# SerialDev-2232-1A.net
KiCad netlist of a schematic drawn in EAGLE
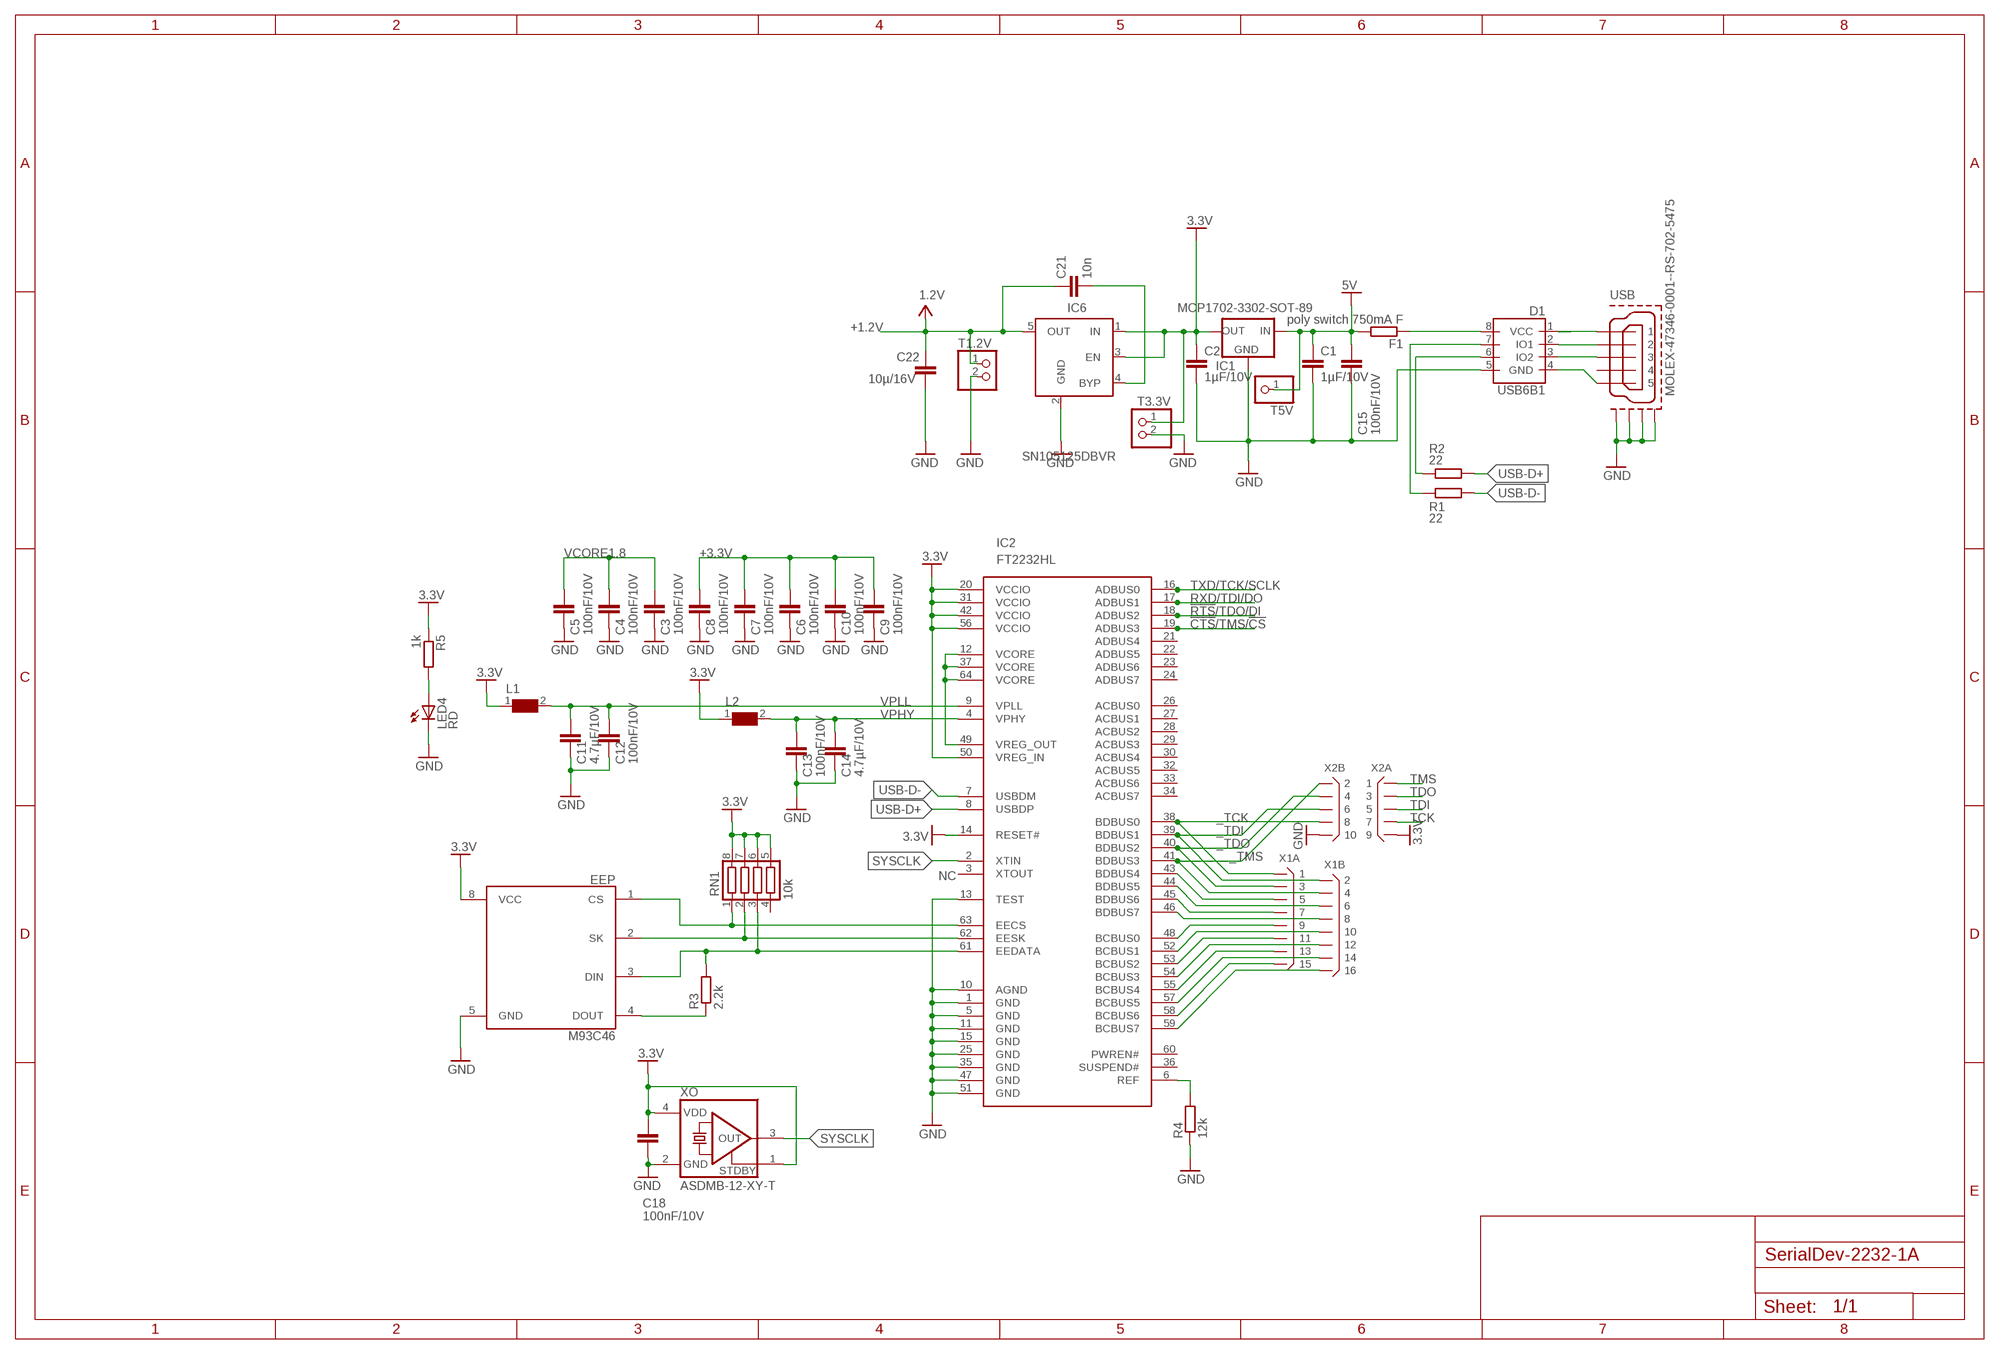
[diagram p0: schematic, sheet 1]

(export (version "E")
  (design (tool "Eeschema 10.0.6"))
  (components
    (comp (ref "C1")
      (value "1µF/10V")
      (footprint "eagle-import:C0805K")
      (libsource (lib "eagle-import") (part "C-EUC0805K"))
    )
    (comp (ref "C2")
      (value "1µF/10V")
      (footprint "eagle-import:C0805K")
      (libsource (lib "eagle-import") (part "C-EUC0805K"))
    )
    (comp (ref "C3")
      (value "100nF/10V")
      (footprint "eagle-import:C0402K")
      (libsource (lib "eagle-import") (part "C-EUC0402K"))
    )
    (comp (ref "C4")
      (value "100nF/10V")
      (footprint "eagle-import:C0402K")
      (libsource (lib "eagle-import") (part "C-EUC0402K"))
    )
    (comp (ref "C5")
      (value "100nF/10V")
      (footprint "eagle-import:C0402K")
      (libsource (lib "eagle-import") (part "C-EUC0402K"))
    )
    (comp (ref "C6")
      (value "100nF/10V")
      (footprint "eagle-import:C0402K")
      (libsource (lib "eagle-import") (part "C-EUC0402K"))
    )
    (comp (ref "C7")
      (value "100nF/10V")
      (footprint "eagle-import:C0402K")
      (libsource (lib "eagle-import") (part "C-EUC0402K"))
    )
    (comp (ref "C8")
      (value "100nF/10V")
      (footprint "eagle-import:C0402K")
      (libsource (lib "eagle-import") (part "C-EUC0402K"))
    )
    (comp (ref "C9")
      (value "100nF/10V")
      (footprint "eagle-import:C0402K")
      (libsource (lib "eagle-import") (part "C-EUC0402K"))
    )
    (comp (ref "C10")
      (value "100nF/10V")
      (footprint "eagle-import:C0402K")
      (libsource (lib "eagle-import") (part "C-EUC0402K"))
    )
    (comp (ref "C11")
      (value "4.7µF/10V")
      (footprint "eagle-import:C0402K")
      (libsource (lib "eagle-import") (part "C-EUC0402K"))
    )
    (comp (ref "C12")
      (value "100nF/10V")
      (footprint "eagle-import:C0402K")
      (libsource (lib "eagle-import") (part "C-EUC0402K"))
    )
    (comp (ref "C13")
      (value "100nF/10V")
      (footprint "eagle-import:C0402K")
      (libsource (lib "eagle-import") (part "C-EUC0402K"))
    )
    (comp (ref "C14")
      (value "4.7µF/10V")
      (footprint "eagle-import:C0402K")
      (libsource (lib "eagle-import") (part "C-EUC0402K"))
    )
    (comp (ref "C15")
      (value "100nF/10V")
      (footprint "eagle-import:C0402K")
      (libsource (lib "eagle-import") (part "C-EUC0402K"))
    )
    (comp (ref "C18")
      (value "100nF/10V")
      (footprint "eagle-import:C0402K")
      (libsource (lib "eagle-import") (part "C-EUC0402K"))
    )
    (comp (ref "C21")
      (value "10n")
      (footprint "eagle-import:C0805K")
      (fields (field (name "PARTNO") "Kemet: C1206C103K5RACTU"))
      (libsource (lib "eagle-import") (part "C-EUC0805K"))
    )
    (comp (ref "C22")
      (value "10µ/16V")
      (footprint "eagle-import:C0805K")
      (fields (field (name "PARTNO") "Vishay Sprague: TR3B106K016C0800"))
      (libsource (lib "eagle-import") (part "C-EUC0805K"))
    )
    (comp (ref "D1")
      (value "USB6B1")
      (footprint "eagle-import:SO08")
      (libsource (lib "eagle-import") (part "USB6B1"))
    )
    (comp (ref "EEP")
      (value "M93C46")
      (footprint "eagle-import:SO08")
      (libsource (lib "eagle-import") (part "M93C46"))
    )
    (comp (ref "F1")
      (value "poly switch 750mA F")
      (footprint "eagle-import:R1206")
      (libsource (lib "eagle-import") (part "R-EU_R1206"))
    )
    (comp (ref "IC1")
      (value "MCP1702-3302-SOT-89")
      (footprint "eagle-import:SOT89-R")
      (libsource (lib "eagle-import") (part "MCP1702--SOT-893302"))
    )
    (comp (ref "IC2")
      (value "FT2232HL")
      (footprint "eagle-import:LQFP-ST-64-2")
      (libsource (lib "eagle-import") (part "FT2232HL"))
    )
    (comp (ref "IC6")
      (value "SN105125DBVR")
      (footprint "eagle-import:SOT23-5")
      (fields (field (name "PARTNO") "LINEAR TECHNOLOGY: LT1761ES5-1.2"))
      (libsource (lib "eagle-import") (part "MIC5219XX"))
    )
    (comp (ref "L1")
      (value "WE-CBF_0603")
      (footprint "eagle-import:0603")
      (libsource (lib "eagle-import") (part "WE-CBF_0603"))
    )
    (comp (ref "L2")
      (value "WE-CBF_0603")
      (footprint "eagle-import:0603")
      (libsource (lib "eagle-import") (part "WE-CBF_0603"))
    )
    (comp (ref "LED4")
      (value "RD")
      (footprint "eagle-import:CHIP-LED0805")
      (libsource (lib "eagle-import") (part "LEDCHIP-LED0805"))
    )
    (comp (ref "R1")
      (value "22")
      (footprint "eagle-import:R0603")
      (libsource (lib "eagle-import") (part "R-EU_R0603"))
    )
    (comp (ref "R2")
      (value "22")
      (footprint "eagle-import:R0603")
      (libsource (lib "eagle-import") (part "R-EU_R0603"))
    )
    (comp (ref "R3")
      (value "2.2k")
      (footprint "eagle-import:R0603")
      (libsource (lib "eagle-import") (part "R-EU_R0603"))
    )
    (comp (ref "R4")
      (value "12k")
      (footprint "eagle-import:R0603")
      (libsource (lib "eagle-import") (part "R-EU_R0603"))
    )
    (comp (ref "R5")
      (value "1k")
      (footprint "eagle-import:R0603")
      (libsource (lib "eagle-import") (part "R-EU_R0603"))
    )
    (comp (ref "RN1")
      (value "10k")
      (footprint "eagle-import:CTS742C083")
      (libsource (lib "eagle-import") (part "CTS742C083"))
    )
    (comp (ref "T1.2V")
      (value "PINHD-1X2")
      (footprint "eagle-import:1X02")
      (libsource (lib "eagle-import") (part "PINHD-1X2"))
    )
    (comp (ref "T3.3V")
      (value "PINHD-1X2")
      (footprint "eagle-import:1X02")
      (libsource (lib "eagle-import") (part "PINHD-1X2"))
    )
    (comp (ref "T5V")
      (value "PINHD-1X1")
      (footprint "eagle-import:1X01")
      (libsource (lib "eagle-import") (part "PINHD-1X1"))
    )
    (comp (ref "USB")
      (value "MOLEX-47346-0001--RS-702-5475")
      (footprint "eagle-import:MOLEX-47364-0001")
      (libsource (lib "eagle-import") (part "MOLEX-47346-0001"))
    )
    (comp (ref "X1")
      (value "X08X2IR")
      (footprint "eagle-import:X16R-IDC")
      (libsource (lib "eagle-import") (part "X08X2IR"))
    )
    (comp (ref "X2")
      (value "X05X2DR")
      (footprint "eagle-import:X10R-DIL")
      (libsource (lib "eagle-import") (part "X05X2DR"))
    )
    (comp (ref "XO")
      (value "ASDMB-12-XY-T")
      (footprint "eagle-import:XO-4-2.5X2.0")
      (fields (field (name "MFG") "ABRACON") (field (name "MFG_PARTNO") "ASDMB-12.000MHZ-XY-T"))
      (libsource (lib "eagle-import") (part "XTAL-ASDMB"))
    )
  )
  (nets
    (net (code "1") (name "/RXD{slash}TDI{slash}DO") (class "Default")
      (node (ref "IC2") (pin "17") (pinfunction "ADBUS1_17") (pintype "bidirectional"))
    )
    (net (code "2") (name "/TCK") (class "Default")
      (node (ref "X2") (pin "7") (pinfunction "7_7") (pintype "bidirectional"))
    )
    (net (code "3") (name "/TDI") (class "Default")
      (node (ref "X2") (pin "5") (pinfunction "5_5") (pintype "bidirectional"))
    )
    (net (code "4") (name "/TDO") (class "Default")
      (node (ref "X2") (pin "3") (pinfunction "3_3") (pintype "bidirectional"))
    )
    (net (code "5") (name "/TMS") (class "Default")
      (node (ref "X2") (pin "1") (pinfunction "1_1") (pintype "bidirectional"))
    )
    (net (code "6") (name "/TXD{slash}TCK{slash}SCLK") (class "Default")
      (node (ref "IC2") (pin "16") (pinfunction "ADBUS0_16") (pintype "bidirectional"))
    )
    (net (code "7") (name "/VCORE1.8") (class "Default")
      (node (ref "C3") (pin "1") (pinfunction "1_1") (pintype "passive"))
      (node (ref "C4") (pin "1") (pinfunction "1_1") (pintype "passive"))
      (node (ref "C5") (pin "1") (pinfunction "1_1") (pintype "passive"))
      (node (ref "IC2") (pin "12") (pinfunction "VCORE_12") (pintype "power_in"))
      (node (ref "IC2") (pin "37") (pinfunction "VCORE_37") (pintype "power_in"))
      (node (ref "IC2") (pin "49") (pinfunction "VREG_OUT_49") (pintype "output"))
      (node (ref "IC2") (pin "64") (pinfunction "VCORE_64") (pintype "power_in"))
    )
    (net (code "8") (name "/VPHY") (class "Default")
      (node (ref "C13") (pin "1") (pinfunction "1_1") (pintype "passive"))
      (node (ref "C14") (pin "1") (pinfunction "1_1") (pintype "passive"))
      (node (ref "IC2") (pin "4") (pinfunction "VPHY_4") (pintype "power_in"))
      (node (ref "L2") (pin "2") (pinfunction "2_2") (pintype "passive"))
    )
    (net (code "9") (name "/VPLL") (class "Default")
      (node (ref "C11") (pin "1") (pinfunction "1_1") (pintype "passive"))
      (node (ref "C12") (pin "1") (pinfunction "1_1") (pintype "passive"))
      (node (ref "IC2") (pin "9") (pinfunction "VPLL_9") (pintype "power_in"))
      (node (ref "L1") (pin "2") (pinfunction "2_2") (pintype "passive"))
    )
    (net (code "10") (name "/_TCK") (class "Default")
      (node (ref "IC2") (pin "38") (pinfunction "BDBUS0_38") (pintype "output"))
      (node (ref "X1") (pin "1") (pinfunction "1_1") (pintype "bidirectional"))
      (node (ref "X2") (pin "8") (pinfunction "8_8") (pintype "bidirectional"))
    )
    (net (code "11") (name "/_TDI") (class "Default")
      (node (ref "IC2") (pin "39") (pinfunction "BDBUS1_39") (pintype "input"))
      (node (ref "X1") (pin "2") (pinfunction "2_2") (pintype "bidirectional"))
      (node (ref "X2") (pin "6") (pinfunction "6_6") (pintype "bidirectional"))
    )
    (net (code "12") (name "/_TDO") (class "Default")
      (node (ref "IC2") (pin "40") (pinfunction "BDBUS2_40") (pintype "output"))
      (node (ref "X1") (pin "3") (pinfunction "3_3") (pintype "bidirectional"))
      (node (ref "X2") (pin "4") (pinfunction "4_4") (pintype "bidirectional"))
    )
    (net (code "13") (name "/_TMS") (class "Default")
      (node (ref "IC2") (pin "41") (pinfunction "BDBUS3_41") (pintype "input"))
      (node (ref "X1") (pin "4") (pinfunction "4_4") (pintype "bidirectional"))
      (node (ref "X2") (pin "2") (pinfunction "2_2") (pintype "bidirectional"))
    )
    (net (code "14") (name "/~{CTS}{slash}TMS{slash}~{CS}") (class "Default")
      (node (ref "IC2") (pin "19") (pinfunction "ADBUS3_19") (pintype "bidirectional"))
    )
    (net (code "15") (name "/~{RTS}{slash}TDO{slash}DI") (class "Default")
      (node (ref "IC2") (pin "18") (pinfunction "ADBUS2_18") (pintype "bidirectional"))
    )
    (net (code "16") (name "1.2V") (class "Default")
      (node (ref "C21") (pin "1") (pinfunction "1_1") (pintype "passive"))
      (node (ref "C22") (pin "1") (pinfunction "1_1") (pintype "passive"))
      (node (ref "IC6") (pin "5") (pinfunction "OUT_5") (pintype "output"))
      (node (ref "T1.2V") (pin "1") (pinfunction "1_1") (pintype "passive"))
    )
    (net (code "17") (name "3.3V") (class "Default")
      (node (ref "C10") (pin "1") (pinfunction "1_1") (pintype "passive"))
      (node (ref "C18") (pin "1") (pinfunction "1_1") (pintype "passive"))
      (node (ref "C2") (pin "1") (pinfunction "1_1") (pintype "passive"))
      (node (ref "C6") (pin "1") (pinfunction "1_1") (pintype "passive"))
      (node (ref "C7") (pin "1") (pinfunction "1_1") (pintype "passive"))
      (node (ref "C8") (pin "1") (pinfunction "1_1") (pintype "passive"))
      (node (ref "C9") (pin "1") (pinfunction "1_1") (pintype "passive"))
      (node (ref "EEP") (pin "8") (pinfunction "VCC_8") (pintype "bidirectional"))
      (node (ref "IC1") (pin "3") (pinfunction "OUT_3") (pintype "passive"))
      (node (ref "IC2") (pin "14") (pinfunction "RESET#_14") (pintype "bidirectional"))
      (node (ref "IC2") (pin "20") (pinfunction "VCCIO_20") (pintype "bidirectional"))
      (node (ref "IC2") (pin "31") (pinfunction "VCCIO_31") (pintype "power_in"))
      (node (ref "IC2") (pin "42") (pinfunction "VCCIO_42") (pintype "bidirectional"))
      (node (ref "IC2") (pin "50") (pinfunction "VREG_IN_50") (pintype "bidirectional"))
      (node (ref "IC2") (pin "56") (pinfunction "VCCIO_56") (pintype "bidirectional"))
      (node (ref "IC6") (pin "1") (pinfunction "IN_1") (pintype "input"))
      (node (ref "IC6") (pin "3") (pinfunction "EN_3") (pintype "input"))
      (node (ref "L1") (pin "1") (pinfunction "1_1") (pintype "passive"))
      (node (ref "L2") (pin "1") (pinfunction "1_1") (pintype "passive"))
      (node (ref "R5") (pin "1") (pinfunction "1_1") (pintype "passive"))
      (node (ref "RN1") (pin "5") (pinfunction "5_5") (pintype "passive"))
      (node (ref "RN1") (pin "6") (pinfunction "6_6") (pintype "passive"))
      (node (ref "RN1") (pin "7") (pinfunction "7_7") (pintype "passive"))
      (node (ref "RN1") (pin "8") (pinfunction "8_8") (pintype "passive"))
      (node (ref "T3.3V") (pin "1") (pinfunction "1_1") (pintype "passive"))
      (node (ref "X2") (pin "9") (pinfunction "9_9") (pintype "bidirectional"))
      (node (ref "XO") (pin "1") (pinfunction "TRI_1") (pintype "input"))
      (node (ref "XO") (pin "4") (pinfunction "VDD_4") (pintype "power_in"))
    )
    (net (code "18") (name "5V") (class "Default")
      (node (ref "C1") (pin "1") (pinfunction "1_1") (pintype "passive"))
      (node (ref "C15") (pin "1") (pinfunction "1_1") (pintype "passive"))
      (node (ref "F1") (pin "2") (pinfunction "2_2") (pintype "passive"))
      (node (ref "IC1") (pin "2") (pinfunction "IN_2") (pintype "input"))
      (node (ref "IC1") (pin "4") (pinfunction "IN_4") (pintype "input"))
      (node (ref "T5V") (pin "1") (pinfunction "1_1") (pintype "passive"))
    )
    (net (code "19") (name "GND") (class "Default")
      (node (ref "C1") (pin "2") (pinfunction "2_2") (pintype "passive"))
      (node (ref "C10") (pin "2") (pinfunction "2_2") (pintype "passive"))
      (node (ref "C11") (pin "2") (pinfunction "2_2") (pintype "passive"))
      (node (ref "C12") (pin "2") (pinfunction "2_2") (pintype "passive"))
      (node (ref "C13") (pin "2") (pinfunction "2_2") (pintype "passive"))
      (node (ref "C14") (pin "2") (pinfunction "2_2") (pintype "passive"))
      (node (ref "C15") (pin "2") (pinfunction "2_2") (pintype "passive"))
      (node (ref "C18") (pin "2") (pinfunction "2_2") (pintype "passive"))
      (node (ref "C2") (pin "2") (pinfunction "2_2") (pintype "passive"))
      (node (ref "C22") (pin "2") (pinfunction "2_2") (pintype "passive"))
      (node (ref "C3") (pin "2") (pinfunction "2_2") (pintype "passive"))
      (node (ref "C4") (pin "2") (pinfunction "2_2") (pintype "passive"))
      (node (ref "C5") (pin "2") (pinfunction "2_2") (pintype "passive"))
      (node (ref "C6") (pin "2") (pinfunction "2_2") (pintype "passive"))
      (node (ref "C7") (pin "2") (pinfunction "2_2") (pintype "passive"))
      (node (ref "C8") (pin "2") (pinfunction "2_2") (pintype "passive"))
      (node (ref "C9") (pin "2") (pinfunction "2_2") (pintype "passive"))
      (node (ref "D1") (pin "5") (pinfunction "GND_5") (pintype "power_in"))
      (node (ref "EEP") (pin "5") (pinfunction "GND_5") (pintype "bidirectional"))
      (node (ref "IC1") (pin "1") (pinfunction "GND_1") (pintype "input"))
      (node (ref "IC2") (pin "1") (pinfunction "GND_1") (pintype "power_in"))
      (node (ref "IC2") (pin "10") (pinfunction "AGND_10") (pintype "power_in"))
      (node (ref "IC2") (pin "11") (pinfunction "GND_11") (pintype "power_in"))
      (node (ref "IC2") (pin "13") (pinfunction "TEST_13") (pintype "input"))
      (node (ref "IC2") (pin "15") (pinfunction "GND_15") (pintype "bidirectional"))
      (node (ref "IC2") (pin "25") (pinfunction "GND_25") (pintype "bidirectional"))
      (node (ref "IC2") (pin "35") (pinfunction "GND_35") (pintype "bidirectional"))
      (node (ref "IC2") (pin "47") (pinfunction "GND_47") (pintype "bidirectional"))
      (node (ref "IC2") (pin "5") (pinfunction "GND_5") (pintype "power_in"))
      (node (ref "IC2") (pin "51") (pinfunction "GND_51") (pintype "bidirectional"))
      (node (ref "IC6") (pin "2") (pinfunction "GND_2") (pintype "power_in"))
      (node (ref "LED4") (pin "C") (pinfunction "C_C") (pintype "passive"))
      (node (ref "R4") (pin "1") (pinfunction "1_1") (pintype "passive"))
      (node (ref "T1.2V") (pin "2") (pinfunction "2_2") (pintype "passive"))
      (node (ref "T3.3V") (pin "2") (pinfunction "2_2") (pintype "passive"))
      (node (ref "USB") (pin "GND1") (pinfunction "GND1_GND1") (pintype "bidirectional"))
      (node (ref "USB") (pin "GND2") (pinfunction "GND2_GND2") (pintype "bidirectional"))
      (node (ref "USB") (pin "GND3") (pinfunction "GND3_GND3") (pintype "bidirectional"))
      (node (ref "USB") (pin "GND4") (pinfunction "GND4_GND4") (pintype "bidirectional"))
      (node (ref "X2") (pin "10") (pinfunction "10_10") (pintype "bidirectional"))
      (node (ref "XO") (pin "2") (pinfunction "GND_2") (pintype "power_in"))
    )
    (net (code "20") (name "Net-(D1-GND-Pad4)") (class "Default")
      (node (ref "D1") (pin "4") (pinfunction "GND_4") (pintype "power_in"))
      (node (ref "USB") (pin "5") (pinfunction "5_5") (pintype "input"))
    )
    (net (code "21") (name "Net-(D1-IO1-Pad2)") (class "Default")
      (node (ref "D1") (pin "2") (pinfunction "IO1_2") (pintype "bidirectional"))
      (node (ref "USB") (pin "2") (pinfunction "2_2") (pintype "input"))
    )
    (net (code "22") (name "Net-(D1-IO1-Pad7)") (class "Default")
      (node (ref "D1") (pin "7") (pinfunction "IO1_7") (pintype "bidirectional"))
      (node (ref "R1") (pin "2") (pinfunction "2_2") (pintype "passive"))
    )
    (net (code "23") (name "Net-(D1-IO2-Pad3)") (class "Default")
      (node (ref "D1") (pin "3") (pinfunction "IO2_3") (pintype "bidirectional"))
      (node (ref "USB") (pin "3") (pinfunction "3_3") (pintype "input"))
    )
    (net (code "24") (name "Net-(D1-IO2-Pad6)") (class "Default")
      (node (ref "D1") (pin "6") (pinfunction "IO2_6") (pintype "bidirectional"))
      (node (ref "R2") (pin "1") (pinfunction "1_1") (pintype "passive"))
    )
    (net (code "25") (name "Net-(D1-VCC-Pad1)") (class "Default")
      (node (ref "D1") (pin "1") (pinfunction "VCC_1") (pintype "power_in"))
      (node (ref "USB") (pin "1") (pinfunction "1_1") (pintype "input"))
    )
    (net (code "26") (name "Net-(D1-VCC-Pad8)") (class "Default")
      (node (ref "D1") (pin "8") (pinfunction "VCC_8") (pintype "power_in"))
      (node (ref "F1") (pin "1") (pinfunction "1_1") (pintype "passive"))
    )
    (net (code "27") (name "Net-(EEP-CS)") (class "Default")
      (node (ref "EEP") (pin "1") (pinfunction "CS_1") (pintype "bidirectional"))
      (node (ref "IC2") (pin "63") (pinfunction "EECS_63") (pintype "bidirectional"))
      (node (ref "RN1") (pin "1") (pinfunction "1_1") (pintype "passive"))
    )
    (net (code "28") (name "Net-(EEP-DIN)") (class "Default")
      (node (ref "EEP") (pin "3") (pinfunction "DIN_3") (pintype "bidirectional"))
      (node (ref "IC2") (pin "61") (pinfunction "EEDATA_61") (pintype "bidirectional"))
      (node (ref "R3") (pin "2") (pinfunction "2_2") (pintype "passive"))
      (node (ref "RN1") (pin "3") (pinfunction "3_3") (pintype "passive"))
    )
    (net (code "29") (name "Net-(EEP-DOUT)") (class "Default")
      (node (ref "EEP") (pin "4") (pinfunction "DOUT_4") (pintype "bidirectional"))
      (node (ref "R3") (pin "1") (pinfunction "1_1") (pintype "passive"))
    )
    (net (code "30") (name "Net-(EEP-SK)") (class "Default")
      (node (ref "EEP") (pin "2") (pinfunction "SK_2") (pintype "bidirectional"))
      (node (ref "IC2") (pin "62") (pinfunction "EESK_62") (pintype "bidirectional"))
      (node (ref "RN1") (pin "2") (pinfunction "2_2") (pintype "passive"))
    )
    (net (code "31") (name "Net-(IC2-BCBUS0)") (class "Default")
      (node (ref "IC2") (pin "48") (pinfunction "BCBUS0_48") (pintype "bidirectional"))
      (node (ref "X1") (pin "9") (pinfunction "9_9") (pintype "bidirectional"))
    )
    (net (code "32") (name "Net-(IC2-BCBUS1)") (class "Default")
      (node (ref "IC2") (pin "52") (pinfunction "BCBUS1_52") (pintype "bidirectional"))
      (node (ref "X1") (pin "10") (pinfunction "10_10") (pintype "bidirectional"))
    )
    (net (code "33") (name "Net-(IC2-BCBUS2)") (class "Default")
      (node (ref "IC2") (pin "53") (pinfunction "BCBUS2_53") (pintype "bidirectional"))
      (node (ref "X1") (pin "11") (pinfunction "11_11") (pintype "bidirectional"))
    )
    (net (code "34") (name "Net-(IC2-BCBUS3)") (class "Default")
      (node (ref "IC2") (pin "54") (pinfunction "BCBUS3_54") (pintype "bidirectional"))
      (node (ref "X1") (pin "12") (pinfunction "12_12") (pintype "bidirectional"))
    )
    (net (code "35") (name "Net-(IC2-BCBUS4)") (class "Default")
      (node (ref "IC2") (pin "55") (pinfunction "BCBUS4_55") (pintype "bidirectional"))
      (node (ref "X1") (pin "13") (pinfunction "13_13") (pintype "bidirectional"))
    )
    (net (code "36") (name "Net-(IC2-BCBUS5)") (class "Default")
      (node (ref "IC2") (pin "57") (pinfunction "BCBUS5_57") (pintype "bidirectional"))
      (node (ref "X1") (pin "14") (pinfunction "14_14") (pintype "bidirectional"))
    )
    (net (code "37") (name "Net-(IC2-BCBUS6)") (class "Default")
      (node (ref "IC2") (pin "58") (pinfunction "BCBUS6_58") (pintype "bidirectional"))
      (node (ref "X1") (pin "15") (pinfunction "15_15") (pintype "bidirectional"))
    )
    (net (code "38") (name "Net-(IC2-BCBUS7)") (class "Default")
      (node (ref "IC2") (pin "59") (pinfunction "BCBUS7_59") (pintype "bidirectional"))
      (node (ref "X1") (pin "16") (pinfunction "16_16") (pintype "bidirectional"))
    )
    (net (code "39") (name "Net-(IC2-BDBUS4)") (class "Default")
      (node (ref "IC2") (pin "43") (pinfunction "BDBUS4_43") (pintype "output"))
      (node (ref "X1") (pin "5") (pinfunction "5_5") (pintype "bidirectional"))
    )
    (net (code "40") (name "Net-(IC2-BDBUS5)") (class "Default")
      (node (ref "IC2") (pin "44") (pinfunction "BDBUS5_44") (pintype "input"))
      (node (ref "X1") (pin "6") (pinfunction "6_6") (pintype "bidirectional"))
    )
    (net (code "41") (name "Net-(IC2-BDBUS6)") (class "Default")
      (node (ref "IC2") (pin "45") (pinfunction "BDBUS6_45") (pintype "input"))
      (node (ref "X1") (pin "7") (pinfunction "7_7") (pintype "bidirectional"))
    )
    (net (code "42") (name "Net-(IC2-BDBUS7)") (class "Default")
      (node (ref "IC2") (pin "46") (pinfunction "BDBUS7_46") (pintype "input"))
      (node (ref "X1") (pin "8") (pinfunction "8_8") (pintype "bidirectional"))
    )
    (net (code "43") (name "Net-(IC2-REF)") (class "Default")
      (node (ref "IC2") (pin "6") (pinfunction "REF_6") (pintype "bidirectional"))
      (node (ref "R4") (pin "2") (pinfunction "2_2") (pintype "passive"))
    )
    (net (code "44") (name "Net-(IC6-BYP)") (class "Default")
      (node (ref "C21") (pin "2") (pinfunction "2_2") (pintype "passive"))
      (node (ref "IC6") (pin "4") (pinfunction "BYP_4") (pintype "passive"))
    )
    (net (code "45") (name "Net-(LED4-PadA)") (class "Default")
      (node (ref "LED4") (pin "A") (pinfunction "A_A") (pintype "passive"))
      (node (ref "R5") (pin "2") (pinfunction "2_2") (pintype "passive"))
    )
    (net (code "46") (name "SYSCLK") (class "Default")
      (node (ref "IC2") (pin "2") (pinfunction "XTIN_2") (pintype "bidirectional"))
      (node (ref "XO") (pin "3") (pinfunction "OUT_3") (pintype "output"))
    )
    (net (code "47") (name "USB-D+") (class "Default")
      (node (ref "IC2") (pin "8") (pinfunction "USBDP_8") (pintype "bidirectional"))
      (node (ref "R2") (pin "2") (pinfunction "2_2") (pintype "passive"))
    )
    (net (code "48") (name "USB-D-") (class "Default")
      (node (ref "IC2") (pin "7") (pinfunction "USBDM_7") (pintype "bidirectional"))
      (node (ref "R1") (pin "1") (pinfunction "1_1") (pintype "passive"))
    )
    (net (code "49") (name "unconnected-(IC2-ACBUS0-Pad26)") (class "Default")
      (node (ref "IC2") (pin "26") (pinfunction "ACBUS0_26") (pintype "bidirectional"))
    )
    (net (code "50") (name "unconnected-(IC2-ACBUS1-Pad27)") (class "Default")
      (node (ref "IC2") (pin "27") (pinfunction "ACBUS1_27") (pintype "bidirectional"))
    )
    (net (code "51") (name "unconnected-(IC2-ACBUS2-Pad28)") (class "Default")
      (node (ref "IC2") (pin "28") (pinfunction "ACBUS2_28") (pintype "bidirectional"))
    )
    (net (code "52") (name "unconnected-(IC2-ACBUS3-Pad29)") (class "Default")
      (node (ref "IC2") (pin "29") (pinfunction "ACBUS3_29") (pintype "bidirectional"))
    )
    (net (code "53") (name "unconnected-(IC2-ACBUS4-Pad30)") (class "Default")
      (node (ref "IC2") (pin "30") (pinfunction "ACBUS4_30") (pintype "bidirectional"))
    )
    (net (code "54") (name "unconnected-(IC2-ACBUS5-Pad32)") (class "Default")
      (node (ref "IC2") (pin "32") (pinfunction "ACBUS5_32") (pintype "bidirectional"))
    )
    (net (code "55") (name "unconnected-(IC2-ACBUS6-Pad33)") (class "Default")
      (node (ref "IC2") (pin "33") (pinfunction "ACBUS6_33") (pintype "bidirectional"))
    )
    (net (code "56") (name "unconnected-(IC2-ACBUS7-Pad34)") (class "Default")
      (node (ref "IC2") (pin "34") (pinfunction "ACBUS7_34") (pintype "bidirectional"))
    )
    (net (code "57") (name "unconnected-(IC2-ADBUS4-Pad21)") (class "Default")
      (node (ref "IC2") (pin "21") (pinfunction "ADBUS4_21") (pintype "bidirectional"))
    )
    (net (code "58") (name "unconnected-(IC2-ADBUS5-Pad22)") (class "Default")
      (node (ref "IC2") (pin "22") (pinfunction "ADBUS5_22") (pintype "bidirectional"))
    )
    (net (code "59") (name "unconnected-(IC2-ADBUS6-Pad23)") (class "Default")
      (node (ref "IC2") (pin "23") (pinfunction "ADBUS6_23") (pintype "bidirectional"))
    )
    (net (code "60") (name "unconnected-(IC2-ADBUS7-Pad24)") (class "Default")
      (node (ref "IC2") (pin "24") (pinfunction "ADBUS7_24") (pintype "bidirectional"))
    )
    (net (code "61") (name "unconnected-(IC2-PWREN#-Pad60)") (class "Default")
      (node (ref "IC2") (pin "60") (pinfunction "PWREN#_60") (pintype "bidirectional"))
    )
    (net (code "62") (name "unconnected-(IC2-SUSPEND#-Pad36)") (class "Default")
      (node (ref "IC2") (pin "36") (pinfunction "SUSPEND#_36") (pintype "bidirectional"))
    )
    (net (code "63") (name "unconnected-(IC2-XTOUT-Pad3)") (class "Default")
      (node (ref "IC2") (pin "3") (pinfunction "XTOUT_3") (pintype "bidirectional"))
    )
    (net (code "64") (name "unconnected-(RN1-Pad4)") (class "Default")
      (node (ref "RN1") (pin "4") (pinfunction "4_4") (pintype "passive"))
    )
    (net (code "65") (name "unconnected-(USB-Pad4)") (class "Default")
      (node (ref "USB") (pin "4") (pinfunction "4_4") (pintype "input"))
    )
  )
)
